# MACH_THU_SCH.net
KiCad netlist of a schematic drawn in Altium Designer
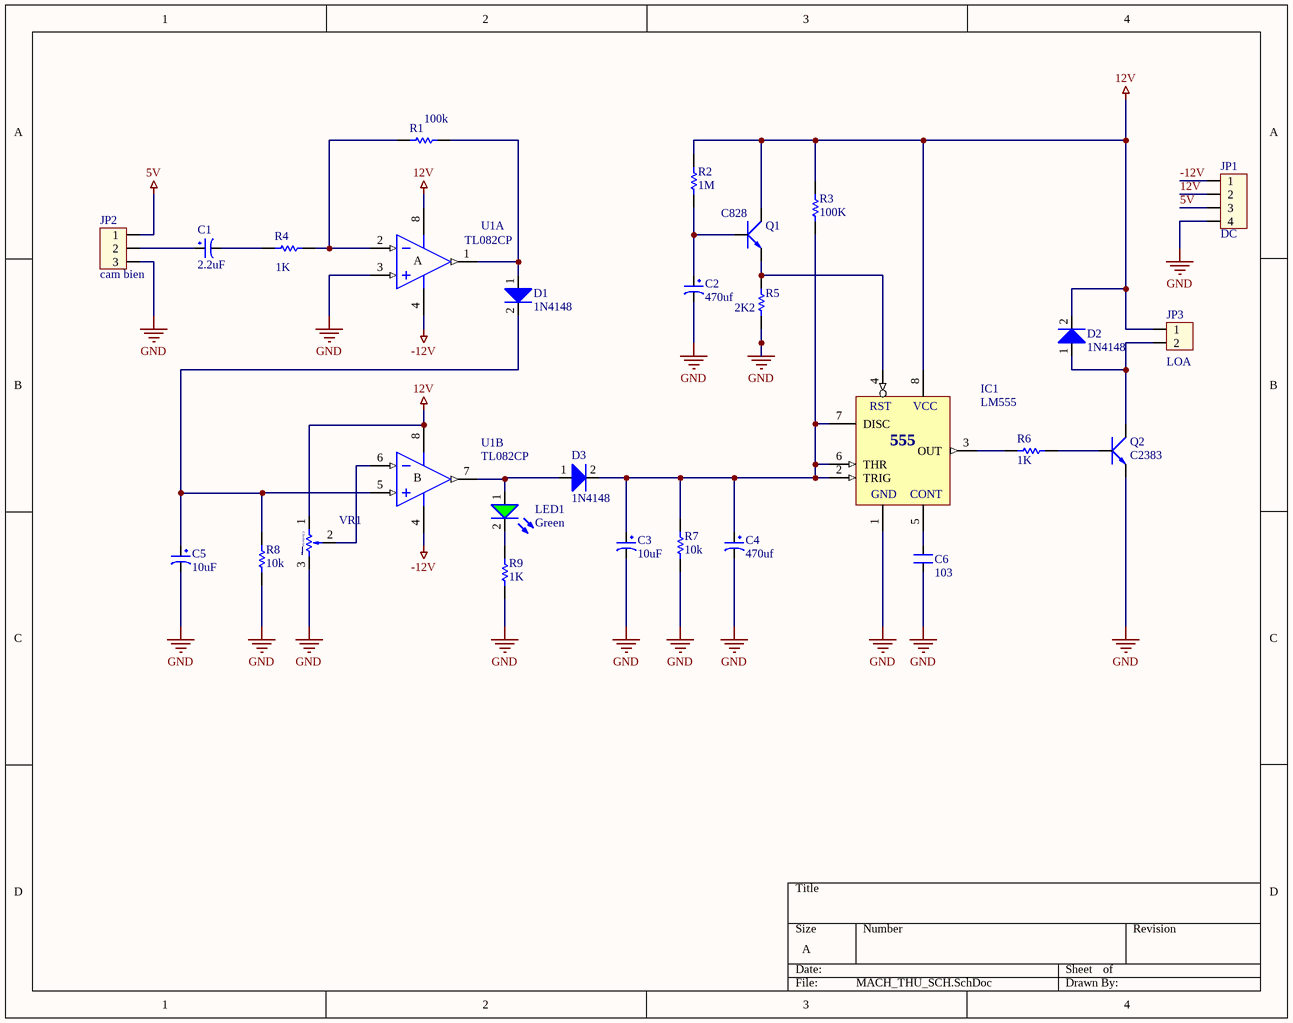
[diagram p0: MACH_THU_SCH.SchDoc]

(export (version "E")
  (design (tool "Eeschema 10.0.6"))
  (components
    (comp (ref "C1")
      (value "2.2uF")
      (footprint "CAP_2_2UF_50V")
      (description "Cap P  0,1uF < 22uF , 16 - 50V")
      (libsource (lib "") (part "CP1_1"))
    )
    (comp (ref "C2")
      (value "470uf")
      (footprint "CAP_470UF_50V")
      (description "Cap 100uF/35V - 470uF/16V")
      (libsource (lib "lpson") (part "CP3"))
    )
    (comp (ref "C3")
      (value "10uF")
      (footprint "CAP_2_2UF_50V")
      (description "Cap P  0,1uF < 22uF , 16 - 50V")
      (libsource (lib "lpson") (part "CP1"))
    )
    (comp (ref "C4")
      (value "470uf")
      (footprint "CAP_470UF_50V")
      (description "Cap 100uF/35V - 470uF/16V")
      (libsource (lib "lpson") (part "CP3"))
    )
    (comp (ref "C5")
      (value "10uF")
      (footprint "CAP_2_2UF_50V")
      (description "Cap P  0,1uF < 22uF , 16 - 50V")
      (libsource (lib "lpson") (part "CP1"))
    )
    (comp (ref "C6")
      (value "103")
      (footprint "Tu gom 104")
      (description "Cap np 682pF => 104pF")
      (libsource (lib "lpson") (part "CN1.5"))
    )
    (comp (ref "D1")
      (value "1N4148")
      (footprint "1N4148")
      (description "Diode HS 200mA 100V DO-35")
      (libsource (lib "lpson") (part "1N4148"))
    )
    (comp (ref "D2")
      (value "1N4148")
      (footprint "1N4148")
      (description "Diode HS 200mA 100V DO-35")
      (libsource (lib "lpson") (part "1N4148"))
    )
    (comp (ref "D3")
      (value "1N4148")
      (footprint "1N4148")
      (description "Diode HS 200mA 100V DO-35")
      (libsource (lib "lpson") (part "1N4148"))
    )
    (comp (ref "IC1")
      (value "LM555")
      (footprint "LM555")
      (description "Timer")
      (libsource (lib "lpson") (part "LM555"))
    )
    (comp (ref "JP1")
      (value "DC")
      (footprint "CON4")
      (description "Connector 4")
      (libsource (lib "lpson") (part "Con4"))
    )
    (comp (ref "JP2")
      (value "cam bien")
      (footprint "SS8550")
      (description "Connector 3")
      (libsource (lib "lpson") (part "Con3"))
    )
    (comp (ref "JP3")
      (value "LOA")
      (footprint "SPEAKER")
      (description "Connector 2")
      (libsource (lib "lpson") (part "Con2"))
    )
    (comp (ref "LED1")
      (value "Green")
      (footprint "LED3G")
      (description "LED Green 3mm")
      (fields (field (name "Comment") "LED_G_3"))
      (libsource (lib "lpson") (part "LED_GREEN_3MM"))
    )
    (comp (ref "Q1")
      (value "C828")
      (footprint "SS8550")
      (description "NPN 600mW, ECB")
      (libsource (lib "lpson") (part "C1815"))
    )
    (comp (ref "Q2")
      (value "C2383")
      (footprint "SS8050")
      (description "NPN 600mW, ECB")
      (libsource (lib "lpson") (part "C1815"))
    )
    (comp (ref "R1")
      (value "100k")
      (footprint "CFR25S")
      (description "Resistor")
      (fields (field (name "Comment") "Res1/4W") (field (name "PUBLISHER") "Altium Limited"))
      (libsource (lib "lpson") (part "Res1/4W"))
    )
    (comp (ref "R2")
      (value "1M")
      (footprint "CFR25S")
      (description "Resistor")
      (fields (field (name "Comment") "Res1/4W") (field (name "PUBLISHER") "Altium Limited"))
      (libsource (lib "lpson") (part "Res1/4W"))
    )
    (comp (ref "R3")
      (value "100K")
      (footprint "CFR25S")
      (description "Resistor")
      (fields (field (name "Comment") "Res1/4W") (field (name "PUBLISHER") "Altium Limited"))
      (libsource (lib "lpson") (part "Res1/4W"))
    )
    (comp (ref "R4")
      (value "1K")
      (footprint "CFR25S")
      (description "Resistor")
      (fields (field (name "Comment") "Res1/4W") (field (name "PUBLISHER") "Altium Limited"))
      (libsource (lib "lpson") (part "Res1/4W"))
    )
    (comp (ref "R5")
      (value "2K2")
      (footprint "CFR25S")
      (description "Resistor")
      (fields (field (name "Comment") "Res1/4W") (field (name "PUBLISHER") "Altium Limited"))
      (libsource (lib "lpson") (part "Res1/4W"))
    )
    (comp (ref "R6")
      (value "1K")
      (footprint "CFR25S")
      (description "Resistor")
      (fields (field (name "Comment") "Res1/4W") (field (name "PUBLISHER") "Altium Limited"))
      (libsource (lib "lpson") (part "Res1/4W"))
    )
    (comp (ref "R7")
      (value "10k")
      (footprint "CFR25S")
      (description "Resistor")
      (fields (field (name "Comment") "Res1/4W") (field (name "PUBLISHER") "Altium Limited"))
      (libsource (lib "lpson") (part "Res1/4W"))
    )
    (comp (ref "R8")
      (value "10k")
      (footprint "CFR25S")
      (description "Resistor")
      (fields (field (name "Comment") "Res1/4W") (field (name "PUBLISHER") "Altium Limited"))
      (libsource (lib "lpson") (part "Res1/4W"))
    )
    (comp (ref "R9")
      (value "1K")
      (footprint "CFR25S")
      (description "Resistor")
      (fields (field (name "Comment") "Res1/4W") (field (name "PUBLISHER") "Altium Limited"))
      (libsource (lib "lpson") (part "Res1/4W"))
    )
    (comp (ref "U1")
      (value "TL082CP")
      (footprint "DIP8")
      (description "JFET-Input Operational Amplifier 18V 3MHz")
      (libsource (lib "lpson") (part "TL082CP"))
    )
    (comp (ref "VR1")
      (value "3306F-1-203")
      (footprint "VR POT 2")
      (description "VAR RES VR3306F 1/5W 20K")
      (libsource (lib "lpson") (part "3306F-1-203"))
    )
  )
  (nets
    (net (code "1") (name "-12V") (class "Default")
      (node (ref "JP1") (pin "1") (pinfunction "1_1") (pintype "passive"))
      (node (ref "U1") (pin "4") (pinfunction "V-_4") (pintype "power_in"))
    )
    (net (code "2") (name "5V") (class "Default")
      (node (ref "JP1") (pin "3") (pinfunction "3_3") (pintype "passive"))
      (node (ref "JP2") (pin "1") (pinfunction "1_1") (pintype "passive"))
    )
    (net (code "3") (name "12V") (class "Default")
      (node (ref "D2") (pin "2") (pinfunction "K_2") (pintype "passive"))
      (node (ref "IC1") (pin "8") (pinfunction "VCC_8") (pintype "power_in"))
      (node (ref "JP1") (pin "2") (pinfunction "2_2") (pintype "passive"))
      (node (ref "JP3") (pin "1") (pinfunction "1_1") (pintype "passive"))
      (node (ref "Q1") (pin "2") (pinfunction "C_2") (pintype "passive"))
      (node (ref "R2") (pin "2") (pinfunction "2_2") (pintype "passive"))
      (node (ref "R3") (pin "2") (pinfunction "2_2") (pintype "passive"))
      (node (ref "U1") (pin "8") (pinfunction "V+_8") (pintype "power_in"))
      (node (ref "VR1") (pin "1") (pinfunction "CCW_1") (pintype "passive"))
    )
    (net (code "4") (name "GND") (class "Default")
      (node (ref "C2") (pin "2") (pinfunction "2_2") (pintype "passive"))
      (node (ref "C3") (pin "2") (pinfunction "2_2") (pintype "passive"))
      (node (ref "C4") (pin "2") (pinfunction "2_2") (pintype "passive"))
      (node (ref "C5") (pin "2") (pinfunction "2_2") (pintype "passive"))
      (node (ref "C6") (pin "1") (pinfunction "1_1") (pintype "passive"))
      (node (ref "IC1") (pin "1") (pinfunction "GND_1") (pintype "power_in"))
      (node (ref "JP1") (pin "4") (pinfunction "4_4") (pintype "passive"))
      (node (ref "JP2") (pin "3") (pinfunction "3_3") (pintype "passive"))
      (node (ref "Q2") (pin "1") (pinfunction "E_1") (pintype "passive"))
      (node (ref "R5") (pin "1") (pinfunction "1_1") (pintype "passive"))
      (node (ref "R7") (pin "1") (pinfunction "1_1") (pintype "passive"))
      (node (ref "R8") (pin "1") (pinfunction "1_1") (pintype "passive"))
      (node (ref "R9") (pin "1") (pinfunction "1_1") (pintype "passive"))
      (node (ref "U1") (pin "3") (pinfunction "IN+_3") (pintype "input"))
      (node (ref "VR1") (pin "3") (pinfunction "CW_3") (pintype "passive"))
    )
    (net (code "5") (name "Net-(C1-Pad1)") (class "Default")
      (node (ref "C1") (pin "1") (pinfunction "1_1") (pintype "passive"))
      (node (ref "JP2") (pin "2") (pinfunction "2_2") (pintype "passive"))
    )
    (net (code "6") (name "Net-(C1-Pad2)") (class "Default")
      (node (ref "C1") (pin "2") (pinfunction "2_2") (pintype "passive"))
      (node (ref "R4") (pin "1") (pinfunction "1_1") (pintype "passive"))
    )
    (net (code "7") (name "Net-(D1-A)") (class "Default")
      (node (ref "D1") (pin "1") (pinfunction "A_1") (pintype "passive"))
      (node (ref "R1") (pin "2") (pinfunction "2_2") (pintype "passive"))
      (node (ref "U1") (pin "1") (pinfunction "OUT_1") (pintype "output"))
    )
    (net (code "8") (name "Net-(D1-K)") (class "Default")
      (node (ref "C5") (pin "1") (pinfunction "1_1") (pintype "passive"))
      (node (ref "D1") (pin "2") (pinfunction "K_2") (pintype "passive"))
      (node (ref "R8") (pin "2") (pinfunction "2_2") (pintype "passive"))
      (node (ref "U1") (pin "5") (pinfunction "IN+_5") (pintype "input"))
    )
    (net (code "9") (name "Net-(D2-A)") (class "Default")
      (node (ref "D2") (pin "1") (pinfunction "A_1") (pintype "passive"))
      (node (ref "JP3") (pin "2") (pinfunction "2_2") (pintype "passive"))
      (node (ref "Q2") (pin "2") (pinfunction "C_2") (pintype "passive"))
    )
    (net (code "10") (name "Net-(D3-A)") (class "Default")
      (node (ref "D3") (pin "1") (pinfunction "A_1") (pintype "passive"))
      (node (ref "LED1") (pin "1") (pinfunction "A_1") (pintype "passive"))
      (node (ref "U1") (pin "7") (pinfunction "OUT_7") (pintype "output"))
    )
    (net (code "11") (name "Net-(D3-K)") (class "Default")
      (node (ref "C3") (pin "1") (pinfunction "1_1") (pintype "passive"))
      (node (ref "C4") (pin "1") (pinfunction "1_1") (pintype "passive"))
      (node (ref "D3") (pin "2") (pinfunction "K_2") (pintype "passive"))
      (node (ref "IC1") (pin "2") (pinfunction "TRIG_2") (pintype "input"))
      (node (ref "IC1") (pin "6") (pinfunction "THR_6") (pintype "input"))
      (node (ref "IC1") (pin "7") (pinfunction "DISC_7") (pintype "open_collector"))
      (node (ref "R3") (pin "1") (pinfunction "1_1") (pintype "passive"))
      (node (ref "R7") (pin "2") (pinfunction "2_2") (pintype "passive"))
    )
    (net (code "12") (name "Net-(IC1-CONT)") (class "Default")
      (node (ref "C6") (pin "2") (pinfunction "2_2") (pintype "passive"))
      (node (ref "IC1") (pin "5") (pinfunction "CONT_5") (pintype "passive"))
    )
    (net (code "13") (name "Net-(IC1-OUT)") (class "Default")
      (node (ref "IC1") (pin "3") (pinfunction "OUT_3") (pintype "output"))
      (node (ref "R6") (pin "2") (pinfunction "2_2") (pintype "passive"))
    )
    (net (code "14") (name "Net-(IC1-RST)") (class "Default")
      (node (ref "IC1") (pin "4") (pinfunction "RST_4") (pintype "input"))
      (node (ref "Q1") (pin "1") (pinfunction "E_1") (pintype "passive"))
      (node (ref "R5") (pin "2") (pinfunction "2_2") (pintype "passive"))
    )
    (net (code "15") (name "Net-(LED1-K)") (class "Default")
      (node (ref "LED1") (pin "2") (pinfunction "K_2") (pintype "passive"))
      (node (ref "R9") (pin "2") (pinfunction "2_2") (pintype "passive"))
    )
    (net (code "16") (name "Net-(Q1-B)") (class "Default")
      (node (ref "C2") (pin "1") (pinfunction "1_1") (pintype "passive"))
      (node (ref "Q1") (pin "3") (pinfunction "B_3") (pintype "passive"))
      (node (ref "R2") (pin "1") (pinfunction "1_1") (pintype "passive"))
    )
    (net (code "17") (name "Net-(Q2-B)") (class "Default")
      (node (ref "Q2") (pin "3") (pinfunction "B_3") (pintype "passive"))
      (node (ref "R6") (pin "1") (pinfunction "1_1") (pintype "passive"))
    )
    (net (code "18") (name "Net-(U1A-IN-)") (class "Default")
      (node (ref "R1") (pin "1") (pinfunction "1_1") (pintype "passive"))
      (node (ref "R4") (pin "2") (pinfunction "2_2") (pintype "passive"))
      (node (ref "U1") (pin "2") (pinfunction "IN-_2") (pintype "input"))
    )
    (net (code "19") (name "Net-(U1B-IN-)") (class "Default")
      (node (ref "U1") (pin "6") (pinfunction "IN-_6") (pintype "input"))
      (node (ref "VR1") (pin "2") (pinfunction "WIPER_2") (pintype "passive"))
    )
  )
)
